# p8x-memory-card.net
KiCad netlist of a schematic drawn in EAGLE
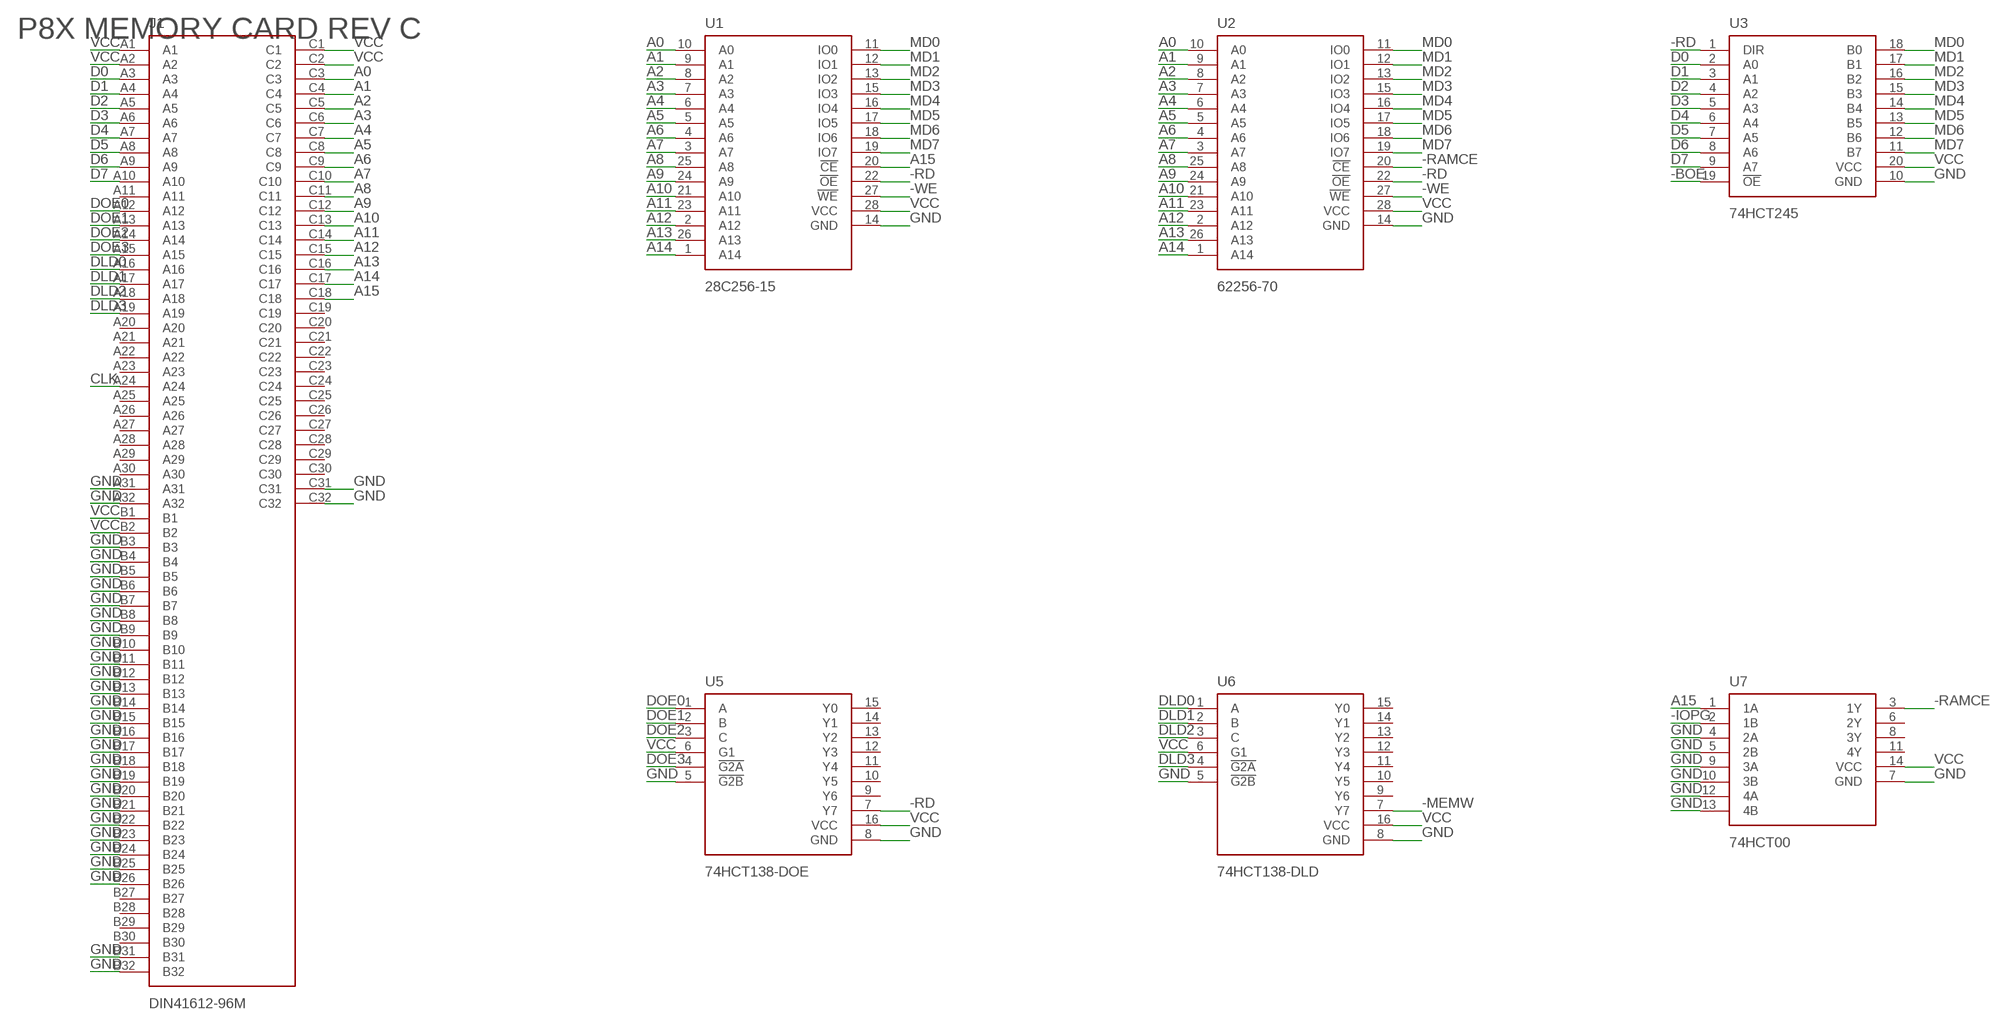
[diagram p0: schematic, sheet 1, part 1 of 2]
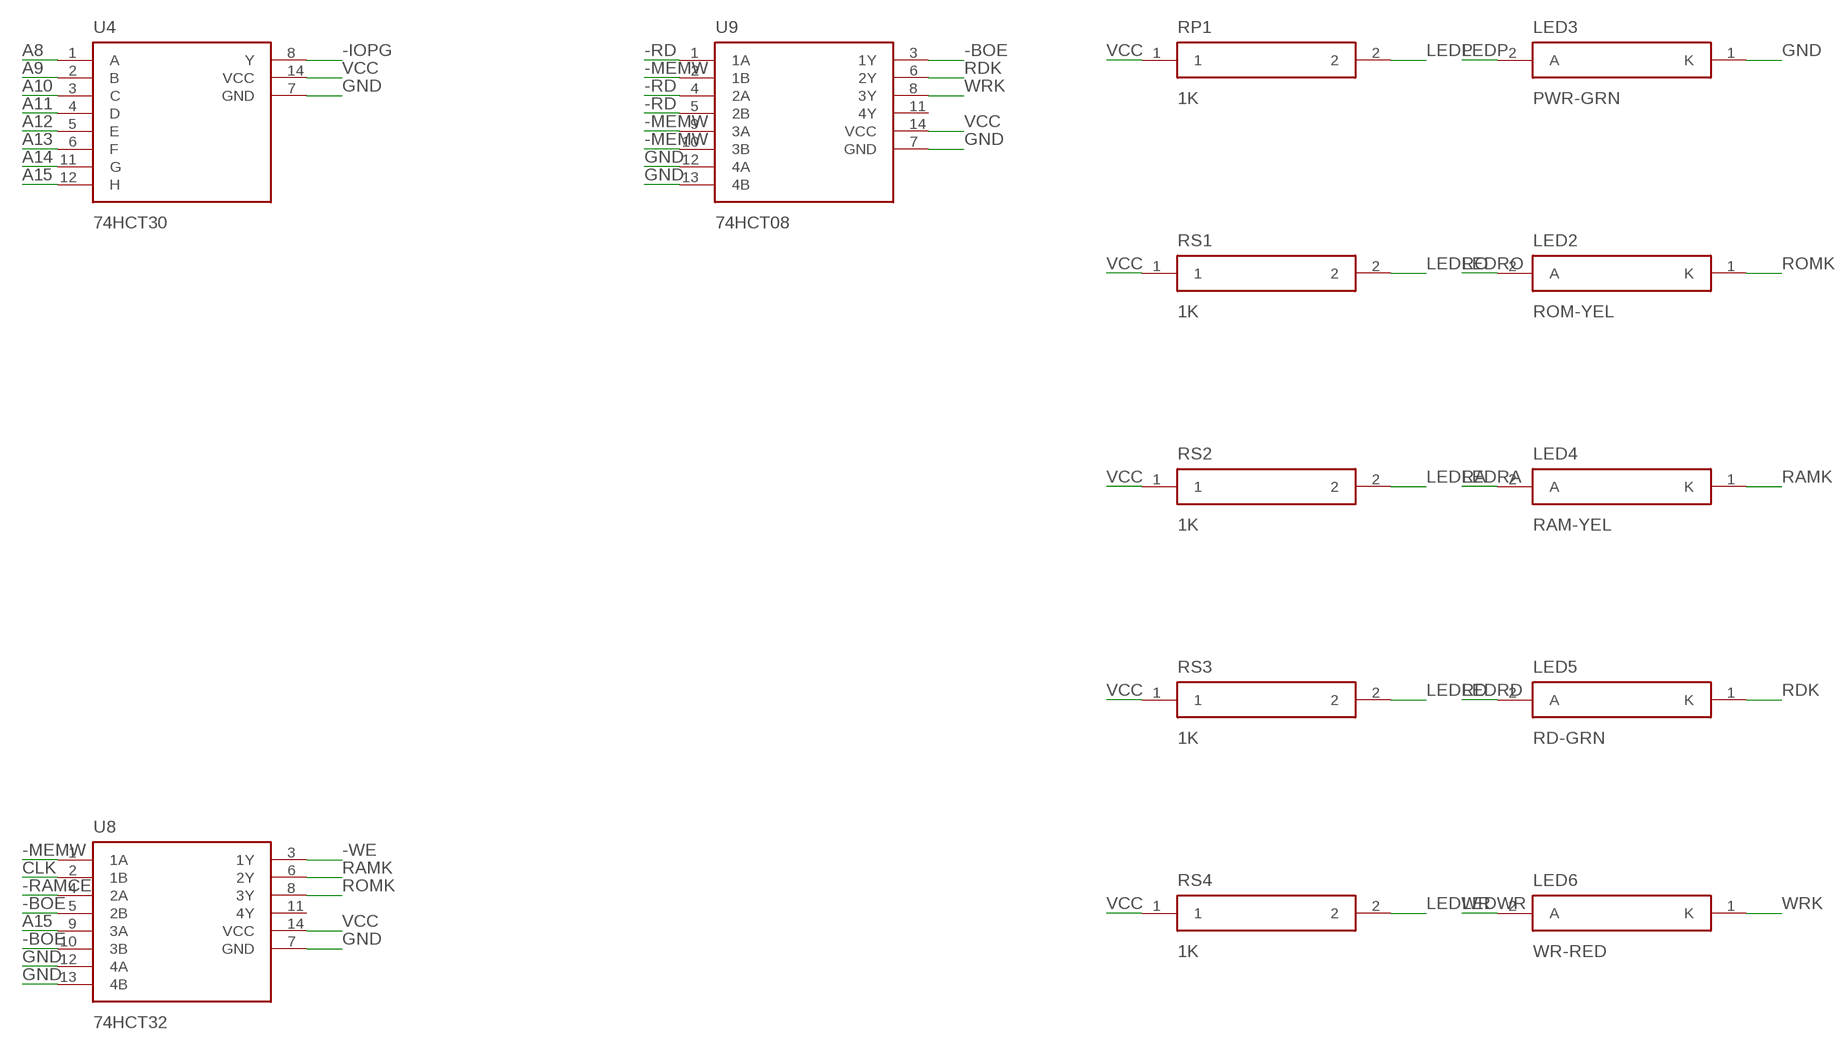
[diagram p1: schematic, sheet 1, part 2 of 2]

(export (version "E")
  (design (tool "Eeschema 10.0.6"))
  (components
    (comp (ref "J1")
      (value "DIN41612-96M")
      (footprint "eagle-import:DIN96")
      (libsource (lib "eagle-import") (part "DIN96"))
    )
    (comp (ref "LED2")
      (value "ROM-YEL")
      (footprint "eagle-import:LED5")
      (libsource (lib "eagle-import") (part "LED"))
    )
    (comp (ref "LED3")
      (value "PWR-GRN")
      (footprint "eagle-import:LED5")
      (libsource (lib "eagle-import") (part "LED"))
    )
    (comp (ref "LED4")
      (value "RAM-YEL")
      (footprint "eagle-import:LED5")
      (libsource (lib "eagle-import") (part "LED"))
    )
    (comp (ref "LED5")
      (value "RD-GRN")
      (footprint "eagle-import:LED5")
      (libsource (lib "eagle-import") (part "LED"))
    )
    (comp (ref "LED6")
      (value "WR-RED")
      (footprint "eagle-import:LED5")
      (libsource (lib "eagle-import") (part "LED"))
    )
    (comp (ref "RP1")
      (value "1K")
      (footprint "eagle-import:R_AXIAL")
      (libsource (lib "eagle-import") (part "RES"))
    )
    (comp (ref "RS1")
      (value "1K")
      (footprint "eagle-import:R_AXIAL")
      (libsource (lib "eagle-import") (part "RES"))
    )
    (comp (ref "RS2")
      (value "1K")
      (footprint "eagle-import:R_AXIAL")
      (libsource (lib "eagle-import") (part "RES"))
    )
    (comp (ref "RS3")
      (value "1K")
      (footprint "eagle-import:R_AXIAL")
      (libsource (lib "eagle-import") (part "RES"))
    )
    (comp (ref "RS4")
      (value "1K")
      (footprint "eagle-import:R_AXIAL")
      (libsource (lib "eagle-import") (part "RES"))
    )
    (comp (ref "U1")
      (value "28C256-15")
      (footprint "eagle-import:DIP28W")
      (libsource (lib "eagle-import") (part "MEM28K8"))
    )
    (comp (ref "U2")
      (value "62256-70")
      (footprint "eagle-import:DIP28W")
      (libsource (lib "eagle-import") (part "MEM28K8"))
    )
    (comp (ref "U3")
      (value "74HCT245")
      (footprint "eagle-import:DIP20")
      (libsource (lib "eagle-import") (part "74245"))
    )
    (comp (ref "U4")
      (value "74HCT30")
      (footprint "eagle-import:DIP14")
      (libsource (lib "eagle-import") (part "7430"))
    )
    (comp (ref "U5")
      (value "74HCT138-DOE")
      (footprint "eagle-import:DIP16")
      (libsource (lib "eagle-import") (part "74138"))
    )
    (comp (ref "U6")
      (value "74HCT138-DLD")
      (footprint "eagle-import:DIP16")
      (libsource (lib "eagle-import") (part "74138"))
    )
    (comp (ref "U7")
      (value "74HCT00")
      (footprint "eagle-import:DIP14")
      (libsource (lib "eagle-import") (part "GATES14"))
    )
    (comp (ref "U8")
      (value "74HCT32")
      (footprint "eagle-import:DIP14")
      (libsource (lib "eagle-import") (part "GATES14"))
    )
    (comp (ref "U9")
      (value "74HCT08")
      (footprint "eagle-import:DIP14")
      (libsource (lib "eagle-import") (part "GATES14"))
    )
  )
  (nets
    (net (code "1") (name "/-BOE") (class "Default")
      (node (ref "U3") (pin "19") (pinfunction "~{OE}_19") (pintype "bidirectional"))
      (node (ref "U8") (pin "10") (pinfunction "3B_10") (pintype "bidirectional"))
      (node (ref "U8") (pin "5") (pinfunction "2B_5") (pintype "bidirectional"))
      (node (ref "U9") (pin "3") (pinfunction "1Y_3") (pintype "bidirectional"))
    )
    (net (code "2") (name "/-IOPG") (class "Default")
      (node (ref "U4") (pin "8") (pinfunction "Y_8") (pintype "bidirectional"))
      (node (ref "U7") (pin "2") (pinfunction "1B_2") (pintype "bidirectional"))
    )
    (net (code "3") (name "/-MEMW") (class "Default")
      (node (ref "U6") (pin "7") (pinfunction "Y7_7") (pintype "bidirectional"))
      (node (ref "U8") (pin "1") (pinfunction "1A_1") (pintype "bidirectional"))
      (node (ref "U9") (pin "10") (pinfunction "3B_10") (pintype "bidirectional"))
      (node (ref "U9") (pin "2") (pinfunction "1B_2") (pintype "bidirectional"))
      (node (ref "U9") (pin "9") (pinfunction "3A_9") (pintype "bidirectional"))
    )
    (net (code "4") (name "/-RAMCE") (class "Default")
      (node (ref "U2") (pin "20") (pinfunction "~{CE}_20") (pintype "bidirectional"))
      (node (ref "U7") (pin "3") (pinfunction "1Y_3") (pintype "bidirectional"))
      (node (ref "U8") (pin "4") (pinfunction "2A_4") (pintype "bidirectional"))
    )
    (net (code "5") (name "/-RD") (class "Default")
      (node (ref "U1") (pin "22") (pinfunction "~{OE}_22") (pintype "bidirectional"))
      (node (ref "U2") (pin "22") (pinfunction "~{OE}_22") (pintype "bidirectional"))
      (node (ref "U3") (pin "1") (pinfunction "DIR_1") (pintype "bidirectional"))
      (node (ref "U5") (pin "7") (pinfunction "Y7_7") (pintype "bidirectional"))
      (node (ref "U9") (pin "1") (pinfunction "1A_1") (pintype "bidirectional"))
      (node (ref "U9") (pin "4") (pinfunction "2A_4") (pintype "bidirectional"))
      (node (ref "U9") (pin "5") (pinfunction "2B_5") (pintype "bidirectional"))
    )
    (net (code "6") (name "/-WE") (class "Default")
      (node (ref "U1") (pin "27") (pinfunction "~{WE}_27") (pintype "bidirectional"))
      (node (ref "U2") (pin "27") (pinfunction "~{WE}_27") (pintype "bidirectional"))
      (node (ref "U8") (pin "3") (pinfunction "1Y_3") (pintype "bidirectional"))
    )
    (net (code "7") (name "/A0") (class "Default")
      (node (ref "J1") (pin "C3") (pinfunction "C3_C3") (pintype "bidirectional"))
      (node (ref "U1") (pin "10") (pinfunction "A0_10") (pintype "bidirectional"))
      (node (ref "U2") (pin "10") (pinfunction "A0_10") (pintype "bidirectional"))
    )
    (net (code "8") (name "/A1") (class "Default")
      (node (ref "J1") (pin "C4") (pinfunction "C4_C4") (pintype "bidirectional"))
      (node (ref "U1") (pin "9") (pinfunction "A1_9") (pintype "bidirectional"))
      (node (ref "U2") (pin "9") (pinfunction "A1_9") (pintype "bidirectional"))
    )
    (net (code "9") (name "/A2") (class "Default")
      (node (ref "J1") (pin "C5") (pinfunction "C5_C5") (pintype "bidirectional"))
      (node (ref "U1") (pin "8") (pinfunction "A2_8") (pintype "bidirectional"))
      (node (ref "U2") (pin "8") (pinfunction "A2_8") (pintype "bidirectional"))
    )
    (net (code "10") (name "/A3") (class "Default")
      (node (ref "J1") (pin "C6") (pinfunction "C6_C6") (pintype "bidirectional"))
      (node (ref "U1") (pin "7") (pinfunction "A3_7") (pintype "bidirectional"))
      (node (ref "U2") (pin "7") (pinfunction "A3_7") (pintype "bidirectional"))
    )
    (net (code "11") (name "/A4") (class "Default")
      (node (ref "J1") (pin "C7") (pinfunction "C7_C7") (pintype "bidirectional"))
      (node (ref "U1") (pin "6") (pinfunction "A4_6") (pintype "bidirectional"))
      (node (ref "U2") (pin "6") (pinfunction "A4_6") (pintype "bidirectional"))
    )
    (net (code "12") (name "/A5") (class "Default")
      (node (ref "J1") (pin "C8") (pinfunction "C8_C8") (pintype "bidirectional"))
      (node (ref "U1") (pin "5") (pinfunction "A5_5") (pintype "bidirectional"))
      (node (ref "U2") (pin "5") (pinfunction "A5_5") (pintype "bidirectional"))
    )
    (net (code "13") (name "/A6") (class "Default")
      (node (ref "J1") (pin "C9") (pinfunction "C9_C9") (pintype "bidirectional"))
      (node (ref "U1") (pin "4") (pinfunction "A6_4") (pintype "bidirectional"))
      (node (ref "U2") (pin "4") (pinfunction "A6_4") (pintype "bidirectional"))
    )
    (net (code "14") (name "/A7") (class "Default")
      (node (ref "J1") (pin "C10") (pinfunction "C10_C10") (pintype "bidirectional"))
      (node (ref "U1") (pin "3") (pinfunction "A7_3") (pintype "bidirectional"))
      (node (ref "U2") (pin "3") (pinfunction "A7_3") (pintype "bidirectional"))
    )
    (net (code "15") (name "/A8") (class "Default")
      (node (ref "J1") (pin "C11") (pinfunction "C11_C11") (pintype "bidirectional"))
      (node (ref "U1") (pin "25") (pinfunction "A8_25") (pintype "bidirectional"))
      (node (ref "U2") (pin "25") (pinfunction "A8_25") (pintype "bidirectional"))
      (node (ref "U4") (pin "1") (pinfunction "A_1") (pintype "bidirectional"))
    )
    (net (code "16") (name "/A9") (class "Default")
      (node (ref "J1") (pin "C12") (pinfunction "C12_C12") (pintype "bidirectional"))
      (node (ref "U1") (pin "24") (pinfunction "A9_24") (pintype "bidirectional"))
      (node (ref "U2") (pin "24") (pinfunction "A9_24") (pintype "bidirectional"))
      (node (ref "U4") (pin "2") (pinfunction "B_2") (pintype "bidirectional"))
    )
    (net (code "17") (name "/A10") (class "Default")
      (node (ref "J1") (pin "C13") (pinfunction "C13_C13") (pintype "bidirectional"))
      (node (ref "U1") (pin "21") (pinfunction "A10_21") (pintype "bidirectional"))
      (node (ref "U2") (pin "21") (pinfunction "A10_21") (pintype "bidirectional"))
      (node (ref "U4") (pin "3") (pinfunction "C_3") (pintype "bidirectional"))
    )
    (net (code "18") (name "/A11") (class "Default")
      (node (ref "J1") (pin "C14") (pinfunction "C14_C14") (pintype "bidirectional"))
      (node (ref "U1") (pin "23") (pinfunction "A11_23") (pintype "bidirectional"))
      (node (ref "U2") (pin "23") (pinfunction "A11_23") (pintype "bidirectional"))
      (node (ref "U4") (pin "4") (pinfunction "D_4") (pintype "bidirectional"))
    )
    (net (code "19") (name "/A12") (class "Default")
      (node (ref "J1") (pin "C15") (pinfunction "C15_C15") (pintype "bidirectional"))
      (node (ref "U1") (pin "2") (pinfunction "A12_2") (pintype "bidirectional"))
      (node (ref "U2") (pin "2") (pinfunction "A12_2") (pintype "bidirectional"))
      (node (ref "U4") (pin "5") (pinfunction "E_5") (pintype "bidirectional"))
    )
    (net (code "20") (name "/A13") (class "Default")
      (node (ref "J1") (pin "C16") (pinfunction "C16_C16") (pintype "bidirectional"))
      (node (ref "U1") (pin "26") (pinfunction "A13_26") (pintype "bidirectional"))
      (node (ref "U2") (pin "26") (pinfunction "A13_26") (pintype "bidirectional"))
      (node (ref "U4") (pin "6") (pinfunction "F_6") (pintype "bidirectional"))
    )
    (net (code "21") (name "/A14") (class "Default")
      (node (ref "J1") (pin "C17") (pinfunction "C17_C17") (pintype "bidirectional"))
      (node (ref "U1") (pin "1") (pinfunction "A14_1") (pintype "bidirectional"))
      (node (ref "U2") (pin "1") (pinfunction "A14_1") (pintype "bidirectional"))
      (node (ref "U4") (pin "11") (pinfunction "G_11") (pintype "bidirectional"))
    )
    (net (code "22") (name "/A15") (class "Default")
      (node (ref "J1") (pin "C18") (pinfunction "C18_C18") (pintype "bidirectional"))
      (node (ref "U1") (pin "20") (pinfunction "~{CE}_20") (pintype "bidirectional"))
      (node (ref "U4") (pin "12") (pinfunction "H_12") (pintype "bidirectional"))
      (node (ref "U7") (pin "1") (pinfunction "1A_1") (pintype "bidirectional"))
      (node (ref "U8") (pin "9") (pinfunction "3A_9") (pintype "bidirectional"))
    )
    (net (code "23") (name "/CLK") (class "Default")
      (node (ref "J1") (pin "A24") (pinfunction "A24_A24") (pintype "bidirectional"))
      (node (ref "U8") (pin "2") (pinfunction "1B_2") (pintype "bidirectional"))
    )
    (net (code "24") (name "/D0") (class "Default")
      (node (ref "J1") (pin "A3") (pinfunction "A3_A3") (pintype "bidirectional"))
      (node (ref "U3") (pin "2") (pinfunction "A0_2") (pintype "bidirectional"))
    )
    (net (code "25") (name "/D1") (class "Default")
      (node (ref "J1") (pin "A4") (pinfunction "A4_A4") (pintype "bidirectional"))
      (node (ref "U3") (pin "3") (pinfunction "A1_3") (pintype "bidirectional"))
    )
    (net (code "26") (name "/D2") (class "Default")
      (node (ref "J1") (pin "A5") (pinfunction "A5_A5") (pintype "bidirectional"))
      (node (ref "U3") (pin "4") (pinfunction "A2_4") (pintype "bidirectional"))
    )
    (net (code "27") (name "/D3") (class "Default")
      (node (ref "J1") (pin "A6") (pinfunction "A6_A6") (pintype "bidirectional"))
      (node (ref "U3") (pin "5") (pinfunction "A3_5") (pintype "bidirectional"))
    )
    (net (code "28") (name "/D4") (class "Default")
      (node (ref "J1") (pin "A7") (pinfunction "A7_A7") (pintype "bidirectional"))
      (node (ref "U3") (pin "6") (pinfunction "A4_6") (pintype "bidirectional"))
    )
    (net (code "29") (name "/D5") (class "Default")
      (node (ref "J1") (pin "A8") (pinfunction "A8_A8") (pintype "bidirectional"))
      (node (ref "U3") (pin "7") (pinfunction "A5_7") (pintype "bidirectional"))
    )
    (net (code "30") (name "/D6") (class "Default")
      (node (ref "J1") (pin "A9") (pinfunction "A9_A9") (pintype "bidirectional"))
      (node (ref "U3") (pin "8") (pinfunction "A6_8") (pintype "bidirectional"))
    )
    (net (code "31") (name "/D7") (class "Default")
      (node (ref "J1") (pin "A10") (pinfunction "A10_A10") (pintype "bidirectional"))
      (node (ref "U3") (pin "9") (pinfunction "A7_9") (pintype "bidirectional"))
    )
    (net (code "32") (name "/DLD0") (class "Default")
      (node (ref "J1") (pin "A16") (pinfunction "A16_A16") (pintype "bidirectional"))
      (node (ref "U6") (pin "1") (pinfunction "A_1") (pintype "bidirectional"))
    )
    (net (code "33") (name "/DLD1") (class "Default")
      (node (ref "J1") (pin "A17") (pinfunction "A17_A17") (pintype "bidirectional"))
      (node (ref "U6") (pin "2") (pinfunction "B_2") (pintype "bidirectional"))
    )
    (net (code "34") (name "/DLD2") (class "Default")
      (node (ref "J1") (pin "A18") (pinfunction "A18_A18") (pintype "bidirectional"))
      (node (ref "U6") (pin "3") (pinfunction "C_3") (pintype "bidirectional"))
    )
    (net (code "35") (name "/DLD3") (class "Default")
      (node (ref "J1") (pin "A19") (pinfunction "A19_A19") (pintype "bidirectional"))
      (node (ref "U6") (pin "4") (pinfunction "~{G2A}_4") (pintype "bidirectional"))
    )
    (net (code "36") (name "/DOE0") (class "Default")
      (node (ref "J1") (pin "A12") (pinfunction "A12_A12") (pintype "bidirectional"))
      (node (ref "U5") (pin "1") (pinfunction "A_1") (pintype "bidirectional"))
    )
    (net (code "37") (name "/DOE1") (class "Default")
      (node (ref "J1") (pin "A13") (pinfunction "A13_A13") (pintype "bidirectional"))
      (node (ref "U5") (pin "2") (pinfunction "B_2") (pintype "bidirectional"))
    )
    (net (code "38") (name "/DOE2") (class "Default")
      (node (ref "J1") (pin "A14") (pinfunction "A14_A14") (pintype "bidirectional"))
      (node (ref "U5") (pin "3") (pinfunction "C_3") (pintype "bidirectional"))
    )
    (net (code "39") (name "/DOE3") (class "Default")
      (node (ref "J1") (pin "A15") (pinfunction "A15_A15") (pintype "bidirectional"))
      (node (ref "U5") (pin "4") (pinfunction "~{G2A}_4") (pintype "bidirectional"))
    )
    (net (code "40") (name "/GND") (class "Default")
      (node (ref "J1") (pin "A31") (pinfunction "A31_A31") (pintype "bidirectional"))
      (node (ref "J1") (pin "A32") (pinfunction "A32_A32") (pintype "bidirectional"))
      (node (ref "J1") (pin "B10") (pinfunction "B10_B10") (pintype "bidirectional"))
      (node (ref "J1") (pin "B11") (pinfunction "B11_B11") (pintype "bidirectional"))
      (node (ref "J1") (pin "B12") (pinfunction "B12_B12") (pintype "bidirectional"))
      (node (ref "J1") (pin "B13") (pinfunction "B13_B13") (pintype "bidirectional"))
      (node (ref "J1") (pin "B14") (pinfunction "B14_B14") (pintype "bidirectional"))
      (node (ref "J1") (pin "B15") (pinfunction "B15_B15") (pintype "bidirectional"))
      (node (ref "J1") (pin "B16") (pinfunction "B16_B16") (pintype "bidirectional"))
      (node (ref "J1") (pin "B17") (pinfunction "B17_B17") (pintype "bidirectional"))
      (node (ref "J1") (pin "B18") (pinfunction "B18_B18") (pintype "bidirectional"))
      (node (ref "J1") (pin "B19") (pinfunction "B19_B19") (pintype "bidirectional"))
      (node (ref "J1") (pin "B20") (pinfunction "B20_B20") (pintype "bidirectional"))
      (node (ref "J1") (pin "B21") (pinfunction "B21_B21") (pintype "bidirectional"))
      (node (ref "J1") (pin "B22") (pinfunction "B22_B22") (pintype "bidirectional"))
      (node (ref "J1") (pin "B23") (pinfunction "B23_B23") (pintype "bidirectional"))
      (node (ref "J1") (pin "B24") (pinfunction "B24_B24") (pintype "bidirectional"))
      (node (ref "J1") (pin "B25") (pinfunction "B25_B25") (pintype "bidirectional"))
      (node (ref "J1") (pin "B26") (pinfunction "B26_B26") (pintype "bidirectional"))
      (node (ref "J1") (pin "B3") (pinfunction "B3_B3") (pintype "bidirectional"))
      (node (ref "J1") (pin "B31") (pinfunction "B31_B31") (pintype "bidirectional"))
      (node (ref "J1") (pin "B32") (pinfunction "B32_B32") (pintype "bidirectional"))
      (node (ref "J1") (pin "B4") (pinfunction "B4_B4") (pintype "bidirectional"))
      (node (ref "J1") (pin "B5") (pinfunction "B5_B5") (pintype "bidirectional"))
      (node (ref "J1") (pin "B6") (pinfunction "B6_B6") (pintype "bidirectional"))
      (node (ref "J1") (pin "B7") (pinfunction "B7_B7") (pintype "bidirectional"))
      (node (ref "J1") (pin "B8") (pinfunction "B8_B8") (pintype "bidirectional"))
      (node (ref "J1") (pin "B9") (pinfunction "B9_B9") (pintype "bidirectional"))
      (node (ref "J1") (pin "C31") (pinfunction "C31_C31") (pintype "bidirectional"))
      (node (ref "J1") (pin "C32") (pinfunction "C32_C32") (pintype "bidirectional"))
      (node (ref "LED3") (pin "1") (pinfunction "K_1") (pintype "bidirectional"))
      (node (ref "U1") (pin "14") (pinfunction "GND_14") (pintype "bidirectional"))
      (node (ref "U2") (pin "14") (pinfunction "GND_14") (pintype "bidirectional"))
      (node (ref "U3") (pin "10") (pinfunction "GND_10") (pintype "bidirectional"))
      (node (ref "U4") (pin "7") (pinfunction "GND_7") (pintype "bidirectional"))
      (node (ref "U5") (pin "5") (pinfunction "~{G2B}_5") (pintype "bidirectional"))
      (node (ref "U5") (pin "8") (pinfunction "GND_8") (pintype "bidirectional"))
      (node (ref "U6") (pin "5") (pinfunction "~{G2B}_5") (pintype "bidirectional"))
      (node (ref "U6") (pin "8") (pinfunction "GND_8") (pintype "bidirectional"))
      (node (ref "U7") (pin "10") (pinfunction "3B_10") (pintype "bidirectional"))
      (node (ref "U7") (pin "12") (pinfunction "4A_12") (pintype "bidirectional"))
      (node (ref "U7") (pin "13") (pinfunction "4B_13") (pintype "bidirectional"))
      (node (ref "U7") (pin "4") (pinfunction "2A_4") (pintype "bidirectional"))
      (node (ref "U7") (pin "5") (pinfunction "2B_5") (pintype "bidirectional"))
      (node (ref "U7") (pin "7") (pinfunction "GND_7") (pintype "bidirectional"))
      (node (ref "U7") (pin "9") (pinfunction "3A_9") (pintype "bidirectional"))
      (node (ref "U8") (pin "12") (pinfunction "4A_12") (pintype "bidirectional"))
      (node (ref "U8") (pin "13") (pinfunction "4B_13") (pintype "bidirectional"))
      (node (ref "U8") (pin "7") (pinfunction "GND_7") (pintype "bidirectional"))
      (node (ref "U9") (pin "12") (pinfunction "4A_12") (pintype "bidirectional"))
      (node (ref "U9") (pin "13") (pinfunction "4B_13") (pintype "bidirectional"))
      (node (ref "U9") (pin "7") (pinfunction "GND_7") (pintype "bidirectional"))
    )
    (net (code "41") (name "/LEDP") (class "Default")
      (node (ref "LED3") (pin "2") (pinfunction "A_2") (pintype "bidirectional"))
      (node (ref "RP1") (pin "2") (pinfunction "2_2") (pintype "bidirectional"))
    )
    (net (code "42") (name "/LEDRA") (class "Default")
      (node (ref "LED4") (pin "2") (pinfunction "A_2") (pintype "bidirectional"))
      (node (ref "RS2") (pin "2") (pinfunction "2_2") (pintype "bidirectional"))
    )
    (net (code "43") (name "/LEDRD") (class "Default")
      (node (ref "LED5") (pin "2") (pinfunction "A_2") (pintype "bidirectional"))
      (node (ref "RS3") (pin "2") (pinfunction "2_2") (pintype "bidirectional"))
    )
    (net (code "44") (name "/LEDRO") (class "Default")
      (node (ref "LED2") (pin "2") (pinfunction "A_2") (pintype "bidirectional"))
      (node (ref "RS1") (pin "2") (pinfunction "2_2") (pintype "bidirectional"))
    )
    (net (code "45") (name "/LEDWR") (class "Default")
      (node (ref "LED6") (pin "2") (pinfunction "A_2") (pintype "bidirectional"))
      (node (ref "RS4") (pin "2") (pinfunction "2_2") (pintype "bidirectional"))
    )
    (net (code "46") (name "/MD0") (class "Default")
      (node (ref "U1") (pin "11") (pinfunction "IO0_11") (pintype "bidirectional"))
      (node (ref "U2") (pin "11") (pinfunction "IO0_11") (pintype "bidirectional"))
      (node (ref "U3") (pin "18") (pinfunction "B0_18") (pintype "bidirectional"))
    )
    (net (code "47") (name "/MD1") (class "Default")
      (node (ref "U1") (pin "12") (pinfunction "IO1_12") (pintype "bidirectional"))
      (node (ref "U2") (pin "12") (pinfunction "IO1_12") (pintype "bidirectional"))
      (node (ref "U3") (pin "17") (pinfunction "B1_17") (pintype "bidirectional"))
    )
    (net (code "48") (name "/MD2") (class "Default")
      (node (ref "U1") (pin "13") (pinfunction "IO2_13") (pintype "bidirectional"))
      (node (ref "U2") (pin "13") (pinfunction "IO2_13") (pintype "bidirectional"))
      (node (ref "U3") (pin "16") (pinfunction "B2_16") (pintype "bidirectional"))
    )
    (net (code "49") (name "/MD3") (class "Default")
      (node (ref "U1") (pin "15") (pinfunction "IO3_15") (pintype "bidirectional"))
      (node (ref "U2") (pin "15") (pinfunction "IO3_15") (pintype "bidirectional"))
      (node (ref "U3") (pin "15") (pinfunction "B3_15") (pintype "bidirectional"))
    )
    (net (code "50") (name "/MD4") (class "Default")
      (node (ref "U1") (pin "16") (pinfunction "IO4_16") (pintype "bidirectional"))
      (node (ref "U2") (pin "16") (pinfunction "IO4_16") (pintype "bidirectional"))
      (node (ref "U3") (pin "14") (pinfunction "B4_14") (pintype "bidirectional"))
    )
    (net (code "51") (name "/MD5") (class "Default")
      (node (ref "U1") (pin "17") (pinfunction "IO5_17") (pintype "bidirectional"))
      (node (ref "U2") (pin "17") (pinfunction "IO5_17") (pintype "bidirectional"))
      (node (ref "U3") (pin "13") (pinfunction "B5_13") (pintype "bidirectional"))
    )
    (net (code "52") (name "/MD6") (class "Default")
      (node (ref "U1") (pin "18") (pinfunction "IO6_18") (pintype "bidirectional"))
      (node (ref "U2") (pin "18") (pinfunction "IO6_18") (pintype "bidirectional"))
      (node (ref "U3") (pin "12") (pinfunction "B6_12") (pintype "bidirectional"))
    )
    (net (code "53") (name "/MD7") (class "Default")
      (node (ref "U1") (pin "19") (pinfunction "IO7_19") (pintype "bidirectional"))
      (node (ref "U2") (pin "19") (pinfunction "IO7_19") (pintype "bidirectional"))
      (node (ref "U3") (pin "11") (pinfunction "B7_11") (pintype "bidirectional"))
    )
    (net (code "54") (name "/RAMK") (class "Default")
      (node (ref "LED4") (pin "1") (pinfunction "K_1") (pintype "bidirectional"))
      (node (ref "U8") (pin "6") (pinfunction "2Y_6") (pintype "bidirectional"))
    )
    (net (code "55") (name "/RDK") (class "Default")
      (node (ref "LED5") (pin "1") (pinfunction "K_1") (pintype "bidirectional"))
      (node (ref "U9") (pin "6") (pinfunction "2Y_6") (pintype "bidirectional"))
    )
    (net (code "56") (name "/ROMK") (class "Default")
      (node (ref "LED2") (pin "1") (pinfunction "K_1") (pintype "bidirectional"))
      (node (ref "U8") (pin "8") (pinfunction "3Y_8") (pintype "bidirectional"))
    )
    (net (code "57") (name "/VCC") (class "Default")
      (node (ref "J1") (pin "A1") (pinfunction "A1_A1") (pintype "bidirectional"))
      (node (ref "J1") (pin "A2") (pinfunction "A2_A2") (pintype "bidirectional"))
      (node (ref "J1") (pin "B1") (pinfunction "B1_B1") (pintype "bidirectional"))
      (node (ref "J1") (pin "B2") (pinfunction "B2_B2") (pintype "bidirectional"))
      (node (ref "J1") (pin "C1") (pinfunction "C1_C1") (pintype "bidirectional"))
      (node (ref "J1") (pin "C2") (pinfunction "C2_C2") (pintype "bidirectional"))
      (node (ref "RP1") (pin "1") (pinfunction "1_1") (pintype "bidirectional"))
      (node (ref "RS1") (pin "1") (pinfunction "1_1") (pintype "bidirectional"))
      (node (ref "RS2") (pin "1") (pinfunction "1_1") (pintype "bidirectional"))
      (node (ref "RS3") (pin "1") (pinfunction "1_1") (pintype "bidirectional"))
      (node (ref "RS4") (pin "1") (pinfunction "1_1") (pintype "bidirectional"))
      (node (ref "U1") (pin "28") (pinfunction "VCC_28") (pintype "bidirectional"))
      (node (ref "U2") (pin "28") (pinfunction "VCC_28") (pintype "bidirectional"))
      (node (ref "U3") (pin "20") (pinfunction "VCC_20") (pintype "bidirectional"))
      (node (ref "U4") (pin "14") (pinfunction "VCC_14") (pintype "bidirectional"))
      (node (ref "U5") (pin "16") (pinfunction "VCC_16") (pintype "bidirectional"))
      (node (ref "U5") (pin "6") (pinfunction "G1_6") (pintype "bidirectional"))
      (node (ref "U6") (pin "16") (pinfunction "VCC_16") (pintype "bidirectional"))
      (node (ref "U6") (pin "6") (pinfunction "G1_6") (pintype "bidirectional"))
      (node (ref "U7") (pin "14") (pinfunction "VCC_14") (pintype "bidirectional"))
      (node (ref "U8") (pin "14") (pinfunction "VCC_14") (pintype "bidirectional"))
      (node (ref "U9") (pin "14") (pinfunction "VCC_14") (pintype "bidirectional"))
    )
    (net (code "58") (name "/WRK") (class "Default")
      (node (ref "LED6") (pin "1") (pinfunction "K_1") (pintype "bidirectional"))
      (node (ref "U9") (pin "8") (pinfunction "3Y_8") (pintype "bidirectional"))
    )
    (net (code "59") (name "unconnected-(J1-PadA11)") (class "Default")
      (node (ref "J1") (pin "A11") (pinfunction "A11_A11") (pintype "bidirectional"))
    )
    (net (code "60") (name "unconnected-(J1-PadA20)") (class "Default")
      (node (ref "J1") (pin "A20") (pinfunction "A20_A20") (pintype "bidirectional"))
    )
    (net (code "61") (name "unconnected-(J1-PadA21)") (class "Default")
      (node (ref "J1") (pin "A21") (pinfunction "A21_A21") (pintype "bidirectional"))
    )
    (net (code "62") (name "unconnected-(J1-PadA22)") (class "Default")
      (node (ref "J1") (pin "A22") (pinfunction "A22_A22") (pintype "bidirectional"))
    )
    (net (code "63") (name "unconnected-(J1-PadA23)") (class "Default")
      (node (ref "J1") (pin "A23") (pinfunction "A23_A23") (pintype "bidirectional"))
    )
    (net (code "64") (name "unconnected-(J1-PadA25)") (class "Default")
      (node (ref "J1") (pin "A25") (pinfunction "A25_A25") (pintype "bidirectional"))
    )
    (net (code "65") (name "unconnected-(J1-PadA26)") (class "Default")
      (node (ref "J1") (pin "A26") (pinfunction "A26_A26") (pintype "bidirectional"))
    )
    (net (code "66") (name "unconnected-(J1-PadA27)") (class "Default")
      (node (ref "J1") (pin "A27") (pinfunction "A27_A27") (pintype "bidirectional"))
    )
    (net (code "67") (name "unconnected-(J1-PadA28)") (class "Default")
      (node (ref "J1") (pin "A28") (pinfunction "A28_A28") (pintype "bidirectional"))
    )
    (net (code "68") (name "unconnected-(J1-PadA29)") (class "Default")
      (node (ref "J1") (pin "A29") (pinfunction "A29_A29") (pintype "bidirectional"))
    )
    (net (code "69") (name "unconnected-(J1-PadA30)") (class "Default")
      (node (ref "J1") (pin "A30") (pinfunction "A30_A30") (pintype "bidirectional"))
    )
    (net (code "70") (name "unconnected-(J1-PadB27)") (class "Default")
      (node (ref "J1") (pin "B27") (pinfunction "B27_B27") (pintype "bidirectional"))
    )
    (net (code "71") (name "unconnected-(J1-PadB28)") (class "Default")
      (node (ref "J1") (pin "B28") (pinfunction "B28_B28") (pintype "bidirectional"))
    )
    (net (code "72") (name "unconnected-(J1-PadB29)") (class "Default")
      (node (ref "J1") (pin "B29") (pinfunction "B29_B29") (pintype "bidirectional"))
    )
    (net (code "73") (name "unconnected-(J1-PadB30)") (class "Default")
      (node (ref "J1") (pin "B30") (pinfunction "B30_B30") (pintype "bidirectional"))
    )
    (net (code "74") (name "unconnected-(J1-PadC19)") (class "Default")
      (node (ref "J1") (pin "C19") (pinfunction "C19_C19") (pintype "bidirectional"))
    )
    (net (code "75") (name "unconnected-(J1-PadC20)") (class "Default")
      (node (ref "J1") (pin "C20") (pinfunction "C20_C20") (pintype "bidirectional"))
    )
    (net (code "76") (name "unconnected-(J1-PadC21)") (class "Default")
      (node (ref "J1") (pin "C21") (pinfunction "C21_C21") (pintype "bidirectional"))
    )
    (net (code "77") (name "unconnected-(J1-PadC22)") (class "Default")
      (node (ref "J1") (pin "C22") (pinfunction "C22_C22") (pintype "bidirectional"))
    )
    (net (code "78") (name "unconnected-(J1-PadC23)") (class "Default")
      (node (ref "J1") (pin "C23") (pinfunction "C23_C23") (pintype "bidirectional"))
    )
    (net (code "79") (name "unconnected-(J1-PadC24)") (class "Default")
      (node (ref "J1") (pin "C24") (pinfunction "C24_C24") (pintype "bidirectional"))
    )
    (net (code "80") (name "unconnected-(J1-PadC25)") (class "Default")
      (node (ref "J1") (pin "C25") (pinfunction "C25_C25") (pintype "bidirectional"))
    )
    (net (code "81") (name "unconnected-(J1-PadC26)") (class "Default")
      (node (ref "J1") (pin "C26") (pinfunction "C26_C26") (pintype "bidirectional"))
    )
    (net (code "82") (name "unconnected-(J1-PadC27)") (class "Default")
      (node (ref "J1") (pin "C27") (pinfunction "C27_C27") (pintype "bidirectional"))
    )
    (net (code "83") (name "unconnected-(J1-PadC28)") (class "Default")
      (node (ref "J1") (pin "C28") (pinfunction "C28_C28") (pintype "bidirectional"))
    )
    (net (code "84") (name "unconnected-(J1-PadC29)") (class "Default")
      (node (ref "J1") (pin "C29") (pinfunction "C29_C29") (pintype "bidirectional"))
    )
    (net (code "85") (name "unconnected-(J1-PadC30)") (class "Default")
      (node (ref "J1") (pin "C30") (pinfunction "C30_C30") (pintype "bidirectional"))
    )
    (net (code "86") (name "unconnected-(U5-Y0-Pad15)") (class "Default")
      (node (ref "U5") (pin "15") (pinfunction "Y0_15") (pintype "bidirectional"))
    )
    (net (code "87") (name "unconnected-(U5-Y1-Pad14)") (class "Default")
      (node (ref "U5") (pin "14") (pinfunction "Y1_14") (pintype "bidirectional"))
    )
    (net (code "88") (name "unconnected-(U5-Y2-Pad13)") (class "Default")
      (node (ref "U5") (pin "13") (pinfunction "Y2_13") (pintype "bidirectional"))
    )
    (net (code "89") (name "unconnected-(U5-Y3-Pad12)") (class "Default")
      (node (ref "U5") (pin "12") (pinfunction "Y3_12") (pintype "bidirectional"))
    )
    (net (code "90") (name "unconnected-(U5-Y4-Pad11)") (class "Default")
      (node (ref "U5") (pin "11") (pinfunction "Y4_11") (pintype "bidirectional"))
    )
    (net (code "91") (name "unconnected-(U5-Y5-Pad10)") (class "Default")
      (node (ref "U5") (pin "10") (pinfunction "Y5_10") (pintype "bidirectional"))
    )
    (net (code "92") (name "unconnected-(U5-Y6-Pad9)") (class "Default")
      (node (ref "U5") (pin "9") (pinfunction "Y6_9") (pintype "bidirectional"))
    )
    (net (code "93") (name "unconnected-(U6-Y0-Pad15)") (class "Default")
      (node (ref "U6") (pin "15") (pinfunction "Y0_15") (pintype "bidirectional"))
    )
    (net (code "94") (name "unconnected-(U6-Y1-Pad14)") (class "Default")
      (node (ref "U6") (pin "14") (pinfunction "Y1_14") (pintype "bidirectional"))
    )
    (net (code "95") (name "unconnected-(U6-Y2-Pad13)") (class "Default")
      (node (ref "U6") (pin "13") (pinfunction "Y2_13") (pintype "bidirectional"))
    )
    (net (code "96") (name "unconnected-(U6-Y3-Pad12)") (class "Default")
      (node (ref "U6") (pin "12") (pinfunction "Y3_12") (pintype "bidirectional"))
    )
    (net (code "97") (name "unconnected-(U6-Y4-Pad11)") (class "Default")
      (node (ref "U6") (pin "11") (pinfunction "Y4_11") (pintype "bidirectional"))
    )
    (net (code "98") (name "unconnected-(U6-Y5-Pad10)") (class "Default")
      (node (ref "U6") (pin "10") (pinfunction "Y5_10") (pintype "bidirectional"))
    )
    (net (code "99") (name "unconnected-(U6-Y6-Pad9)") (class "Default")
      (node (ref "U6") (pin "9") (pinfunction "Y6_9") (pintype "bidirectional"))
    )
    (net (code "100") (name "unconnected-(U7-2Y-Pad6)") (class "Default")
      (node (ref "U7") (pin "6") (pinfunction "2Y_6") (pintype "bidirectional"))
    )
    (net (code "101") (name "unconnected-(U7-3Y-Pad8)") (class "Default")
      (node (ref "U7") (pin "8") (pinfunction "3Y_8") (pintype "bidirectional"))
    )
    (net (code "102") (name "unconnected-(U7-4Y-Pad11)") (class "Default")
      (node (ref "U7") (pin "11") (pinfunction "4Y_11") (pintype "bidirectional"))
    )
    (net (code "103") (name "unconnected-(U8-4Y-Pad11)") (class "Default")
      (node (ref "U8") (pin "11") (pinfunction "4Y_11") (pintype "bidirectional"))
    )
    (net (code "104") (name "unconnected-(U9-4Y-Pad11)") (class "Default")
      (node (ref "U9") (pin "11") (pinfunction "4Y_11") (pintype "bidirectional"))
    )
  )
)
